# Low-Frequency-LC-Oscillator-Hartley.net
KiCad netlist of a schematic drawn in EAGLE
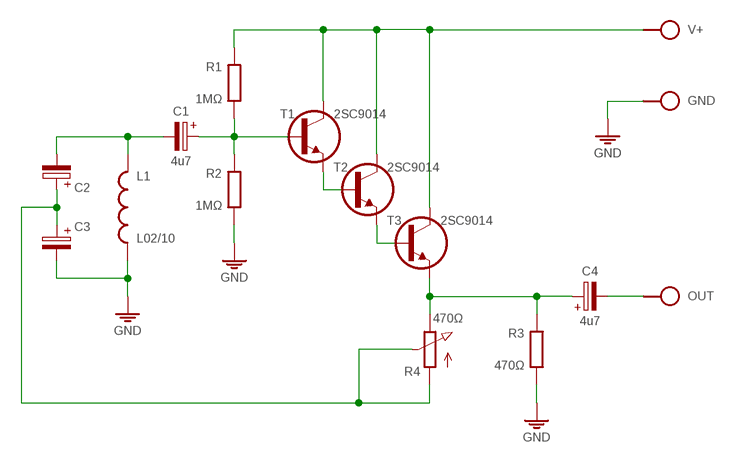
[diagram p0: schematic, sheet 1]

(export (version "E")
  (design (tool "Eeschema 10.0.6"))
  (components
    (comp (ref "C1")
      (value "4u7")
      (footprint "eagle-import:E2,5-3")
      (libsource (lib "eagle-import") (part "CPOLE2,5-3"))
    )
    (comp (ref "C2")
      (value "CPOLE2.5-5")
      (footprint "eagle-import:E2,5-5")
      (libsource (lib "eagle-import") (part "CPOLE2.5-5"))
    )
    (comp (ref "C3")
      (value "CPOLE2.5-5")
      (footprint "eagle-import:E2,5-5")
      (libsource (lib "eagle-import") (part "CPOLE2.5-5"))
    )
    (comp (ref "C4")
      (value "4u7")
      (footprint "eagle-import:E2,5-3")
      (libsource (lib "eagle-import") (part "CPOLE2,5-3"))
    )
    (comp (ref "GND")
      (value "SPAD")
      (footprint "eagle-import:SPAD")
      (libsource (lib "eagle-import") (part "SPAD"))
    )
    (comp (ref "L1")
      (value "L02/10")
      (footprint "eagle-import:L-03_10V")
      (libsource (lib "eagle-import") (part "L02/10"))
    )
    (comp (ref "OUT")
      (value "SPAD")
      (footprint "eagle-import:SPAD")
      (libsource (lib "eagle-import") (part "SPAD"))
    )
    (comp (ref "R1")
      (value "1MΩ")
      (footprint "eagle-import:0204_15")
      (libsource (lib "eagle-import") (part "R0204/15"))
    )
    (comp (ref "R2")
      (value "1MΩ")
      (footprint "eagle-import:0204_12-V")
      (libsource (lib "eagle-import") (part "R0204/12-V"))
    )
    (comp (ref "R3")
      (value "470Ω")
      (footprint "eagle-import:0204_12")
      (libsource (lib "eagle-import") (part "R0204/12"))
    )
    (comp (ref "R4")
      (value "470Ω")
      (footprint "eagle-import:POT")
      (libsource (lib "eagle-import") (part "POT"))
    )
    (comp (ref "T1")
      (value "2SC9014")
      (footprint "eagle-import:TO92-EBC")
      (libsource (lib "eagle-import") (part "2SC9014"))
    )
    (comp (ref "T2")
      (value "2SC9014")
      (footprint "eagle-import:TO92-EBC")
      (libsource (lib "eagle-import") (part "2SC9014"))
    )
    (comp (ref "T3")
      (value "2SC9014")
      (footprint "eagle-import:TO92-EBC")
      (libsource (lib "eagle-import") (part "2SC9014"))
    )
    (comp (ref "V+")
      (value "SPAD")
      (footprint "eagle-import:SPAD")
      (libsource (lib "eagle-import") (part "SPAD"))
    )
  )
  (nets
    (net (code "1") (name "GND") (class "Default")
      (node (ref "C3") (pin "-") (pinfunction "-_-") (pintype "passive"))
      (node (ref "GND") (pin "1") (pinfunction "P$1_1") (pintype "bidirectional"))
      (node (ref "L1") (pin "2") (pinfunction "2_2") (pintype "passive"))
      (node (ref "R2") (pin "1") (pinfunction "1_1") (pintype "passive"))
      (node (ref "R3") (pin "1") (pinfunction "1_1") (pintype "passive"))
    )
    (net (code "2") (name "Net-(C1-Pad+)") (class "Default")
      (node (ref "C1") (pin "+") (pinfunction "+_+") (pintype "passive"))
      (node (ref "R1") (pin "1") (pinfunction "1_1") (pintype "passive"))
      (node (ref "R2") (pin "2") (pinfunction "2_2") (pintype "passive"))
      (node (ref "T1") (pin "B") (pinfunction "B_B") (pintype "passive"))
    )
    (net (code "3") (name "Net-(C1-Pad-)") (class "Default")
      (node (ref "C1") (pin "-") (pinfunction "-_-") (pintype "passive"))
      (node (ref "C2") (pin "-") (pinfunction "-_-") (pintype "passive"))
      (node (ref "L1") (pin "1") (pinfunction "1_1") (pintype "passive"))
    )
    (net (code "4") (name "Net-(OUT-P$1)") (class "Default")
      (node (ref "C4") (pin "-") (pinfunction "-_-") (pintype "passive"))
      (node (ref "OUT") (pin "1") (pinfunction "P$1_1") (pintype "bidirectional"))
    )
    (net (code "5") (name "Net-(R4-A)") (class "Default")
      (node (ref "C2") (pin "+") (pinfunction "+_+") (pintype "passive"))
      (node (ref "C3") (pin "+") (pinfunction "+_+") (pintype "passive"))
      (node (ref "R4") (pin "1") (pinfunction "A_1") (pintype "passive"))
      (node (ref "R4") (pin "2") (pinfunction "S_2") (pintype "passive"))
    )
    (net (code "6") (name "Net-(R4-E)") (class "Default")
      (node (ref "C4") (pin "+") (pinfunction "+_+") (pintype "passive"))
      (node (ref "R3") (pin "2") (pinfunction "2_2") (pintype "passive"))
      (node (ref "R4") (pin "3") (pinfunction "E_3") (pintype "passive"))
      (node (ref "T3") (pin "E") (pinfunction "E_E") (pintype "passive"))
    )
    (net (code "7") (name "Net-(T1-PadE)") (class "Default")
      (node (ref "T1") (pin "E") (pinfunction "E_E") (pintype "passive"))
      (node (ref "T2") (pin "B") (pinfunction "B_B") (pintype "passive"))
    )
    (net (code "8") (name "Net-(T2-PadE)") (class "Default")
      (node (ref "T2") (pin "E") (pinfunction "E_E") (pintype "passive"))
      (node (ref "T3") (pin "B") (pinfunction "B_B") (pintype "passive"))
    )
    (net (code "9") (name "Net-(V+-P$1)") (class "Default")
      (node (ref "R1") (pin "2") (pinfunction "2_2") (pintype "passive"))
      (node (ref "T1") (pin "C") (pinfunction "C_C") (pintype "passive"))
      (node (ref "T2") (pin "C") (pinfunction "C_C") (pintype "passive"))
      (node (ref "T3") (pin "C") (pinfunction "C_C") (pintype "passive"))
      (node (ref "V+") (pin "1") (pinfunction "P$1_1") (pintype "bidirectional"))
    )
  )
)
